# VALVEBOARD_ValveDrive4.net
KiCad netlist of a schematic drawn in Altium Designer
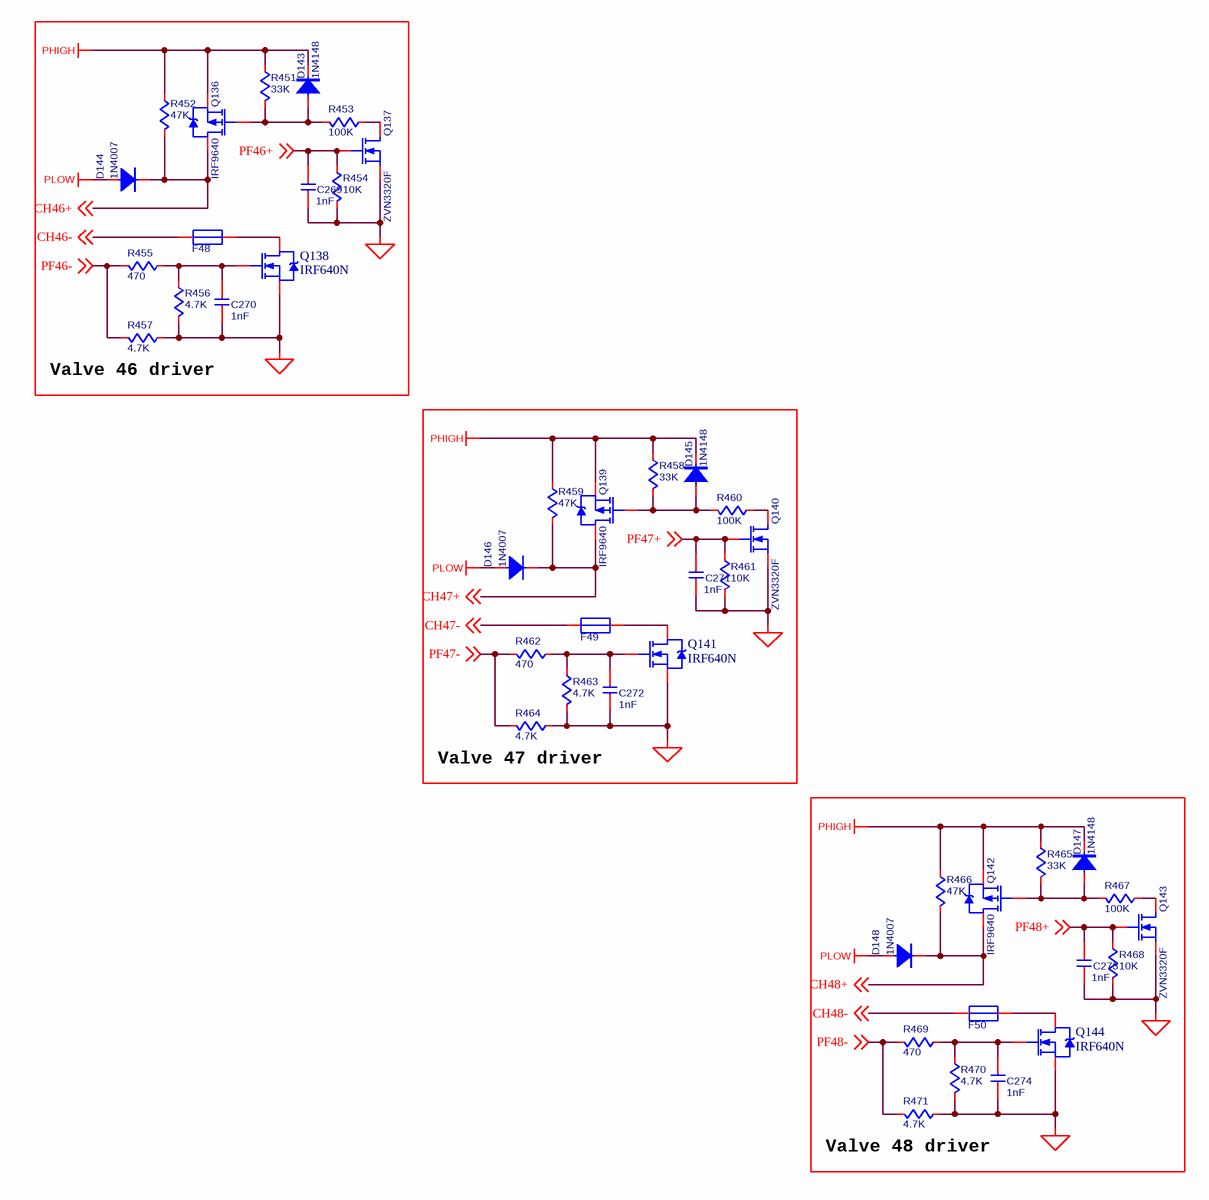
[diagram p0: VALVEBOARD_ValveDrive4.SchDoc]

(export (version "E")
  (design (tool "Eeschema 10.0.6"))
  (components
    (comp (ref "C269")
      (value "1nF")
      (footprint "zynq:C0603")
      (fields (field (name "VOLTAGE") "25V") (field (name "Comment") "C-NOMO"))
      (libsource (lib "zynq") (part "C-NOMO"))
    )
    (comp (ref "C270")
      (value "1nF")
      (footprint "zynq:C0603")
      (fields (field (name "VOLTAGE") "25V") (field (name "Comment") "C-NOMO"))
      (libsource (lib "zynq") (part "C-NOMO"))
    )
    (comp (ref "C271")
      (value "1nF")
      (footprint "zynq:C0603")
      (fields (field (name "VOLTAGE") "25V") (field (name "Comment") "C-NOMO"))
      (libsource (lib "zynq") (part "C-NOMO"))
    )
    (comp (ref "C272")
      (value "1nF")
      (footprint "zynq:C0603")
      (fields (field (name "VOLTAGE") "25V") (field (name "Comment") "C-NOMO"))
      (libsource (lib "zynq") (part "C-NOMO"))
    )
    (comp (ref "C273")
      (value "1nF")
      (footprint "zynq:C0603")
      (fields (field (name "VOLTAGE") "25V") (field (name "Comment") "C-NOMO"))
      (libsource (lib "zynq") (part "C-NOMO"))
    )
    (comp (ref "C274")
      (value "1nF")
      (footprint "zynq:C0603")
      (fields (field (name "VOLTAGE") "25V") (field (name "Comment") "C-NOMO"))
      (libsource (lib "zynq") (part "C-NOMO"))
    )
    (comp (ref "D143") (value "1N4148") (footprint "SOD-123") (libsource (lib "zynq") (part "DIOD1")))
    (comp (ref "D144") (value "1N4007") (footprint "zynq:1N4148") (libsource (lib "") (part "DIOD1_1")))
    (comp (ref "D145") (value "1N4148") (footprint "SOD-123") (libsource (lib "zynq") (part "DIOD1")))
    (comp (ref "D146") (value "1N4007") (footprint "zynq:1N4148") (libsource (lib "") (part "DIOD1_1")))
    (comp (ref "D147") (value "1N4148") (footprint "SOD-123") (libsource (lib "zynq") (part "DIOD1")))
    (comp (ref "D148") (value "1N4007") (footprint "zynq:1N4148") (libsource (lib "") (part "DIOD1_1")))
    (comp (ref "F48") (value "F50") (footprint "zynq:F-TH") (libsource (lib "zynq") (part "F50")))
    (comp (ref "F49") (value "F50") (footprint "zynq:F-TH") (libsource (lib "zynq") (part "F50")))
    (comp (ref "F50") (value "F50") (footprint "zynq:F-TH") (libsource (lib "zynq") (part "F50")))
    (comp (ref "Q136")
      (value "IRF9640")
      (footprint "TO-220AB")
      (description "P-Channel Power MOSFET")
      (fields (field (name "PUBLISHER") "Altium Limited"))
      (libsource (lib "zynq") (part "IRF9640"))
    )
    (comp (ref "Q137")
      (value "ZVN3320F")
      (footprint "zynq:ZVN3320F")
      (description "N-Channel MOSFET")
      (fields (field (name "PUBLISHER") "Altium Limited"))
      (libsource (lib "zynq") (part "ZVN3320F"))
    )
    (comp (ref "Q138")
      (value "IRF640N")
      (footprint "zynq:TO-220AB")
      (description "N-Channel Power MOSFET")
      (fields (field (name "PUBLISHER") "Altium Limited"))
      (libsource (lib "zynq") (part "IRF640N"))
    )
    (comp (ref "Q139")
      (value "IRF9640")
      (footprint "TO-220AB")
      (description "P-Channel Power MOSFET")
      (fields (field (name "PUBLISHER") "Altium Limited"))
      (libsource (lib "zynq") (part "IRF9640"))
    )
    (comp (ref "Q140")
      (value "ZVN3320F")
      (footprint "zynq:ZVN3320F")
      (description "N-Channel MOSFET")
      (fields (field (name "PUBLISHER") "Altium Limited"))
      (libsource (lib "zynq") (part "ZVN3320F"))
    )
    (comp (ref "Q141")
      (value "IRF640N")
      (footprint "zynq:TO-220AB")
      (description "N-Channel Power MOSFET")
      (fields (field (name "PUBLISHER") "Altium Limited"))
      (libsource (lib "zynq") (part "IRF640N"))
    )
    (comp (ref "Q142")
      (value "IRF9640")
      (footprint "TO-220AB")
      (description "P-Channel Power MOSFET")
      (fields (field (name "PUBLISHER") "Altium Limited"))
      (libsource (lib "zynq") (part "IRF9640"))
    )
    (comp (ref "Q143")
      (value "ZVN3320F")
      (footprint "zynq:ZVN3320F")
      (description "N-Channel MOSFET")
      (fields (field (name "PUBLISHER") "Altium Limited"))
      (libsource (lib "zynq") (part "ZVN3320F"))
    )
    (comp (ref "Q144")
      (value "IRF640N")
      (footprint "zynq:TO-220AB")
      (description "N-Channel Power MOSFET")
      (fields (field (name "PUBLISHER") "Altium Limited"))
      (libsource (lib "zynq") (part "IRF640N"))
    )
    (comp (ref "R451")
      (value "33K")
      (footprint "zynq:R0603")
      (fields (field (name "Comment") "R"))
      (libsource (lib "zynq") (part "R"))
    )
    (comp (ref "R452")
      (value "47K")
      (footprint "R2512")
      (fields (field (name "Comment") "R"))
      (libsource (lib "zynq") (part "R"))
    )
    (comp (ref "R453")
      (value "100K")
      (footprint "zynq:R0603")
      (fields (field (name "Comment") "R"))
      (libsource (lib "zynq") (part "R"))
    )
    (comp (ref "R454")
      (value "10K")
      (footprint "zynq:R0603")
      (fields (field (name "Comment") "R"))
      (libsource (lib "zynq") (part "R"))
    )
    (comp (ref "R455")
      (value "470")
      (footprint "zynq:R0402")
      (fields (field (name "Comment") "R"))
      (libsource (lib "zynq") (part "R"))
    )
    (comp (ref "R456")
      (value "4.7K")
      (footprint "zynq:R0402")
      (fields (field (name "Comment") "R"))
      (libsource (lib "zynq") (part "R"))
    )
    (comp (ref "R457")
      (value "4.7K")
      (footprint "zynq:R0402")
      (fields (field (name "Comment") "R"))
      (libsource (lib "zynq") (part "R"))
    )
    (comp (ref "R458")
      (value "33K")
      (footprint "zynq:R0603")
      (fields (field (name "Comment") "R"))
      (libsource (lib "zynq") (part "R"))
    )
    (comp (ref "R459")
      (value "47K")
      (footprint "R2512")
      (fields (field (name "Comment") "R"))
      (libsource (lib "zynq") (part "R"))
    )
    (comp (ref "R460")
      (value "100K")
      (footprint "zynq:R0603")
      (fields (field (name "Comment") "R"))
      (libsource (lib "zynq") (part "R"))
    )
    (comp (ref "R461")
      (value "10K")
      (footprint "zynq:R0603")
      (fields (field (name "Comment") "R"))
      (libsource (lib "zynq") (part "R"))
    )
    (comp (ref "R462")
      (value "470")
      (footprint "zynq:R0402")
      (fields (field (name "Comment") "R"))
      (libsource (lib "zynq") (part "R"))
    )
    (comp (ref "R463")
      (value "4.7K")
      (footprint "zynq:R0402")
      (fields (field (name "Comment") "R"))
      (libsource (lib "zynq") (part "R"))
    )
    (comp (ref "R464")
      (value "4.7K")
      (footprint "zynq:R0402")
      (fields (field (name "Comment") "R"))
      (libsource (lib "zynq") (part "R"))
    )
    (comp (ref "R465")
      (value "33K")
      (footprint "zynq:R0603")
      (fields (field (name "Comment") "R"))
      (libsource (lib "zynq") (part "R"))
    )
    (comp (ref "R466")
      (value "47K")
      (footprint "R2512")
      (fields (field (name "Comment") "R"))
      (libsource (lib "zynq") (part "R"))
    )
    (comp (ref "R467")
      (value "100K")
      (footprint "zynq:R0603")
      (fields (field (name "Comment") "R"))
      (libsource (lib "zynq") (part "R"))
    )
    (comp (ref "R468")
      (value "10K")
      (footprint "zynq:R0603")
      (fields (field (name "Comment") "R"))
      (libsource (lib "zynq") (part "R"))
    )
    (comp (ref "R469")
      (value "470")
      (footprint "zynq:R0402")
      (fields (field (name "Comment") "R"))
      (libsource (lib "zynq") (part "R"))
    )
    (comp (ref "R470")
      (value "4.7K")
      (footprint "zynq:R0402")
      (fields (field (name "Comment") "R"))
      (libsource (lib "zynq") (part "R"))
    )
    (comp (ref "R471")
      (value "4.7K")
      (footprint "zynq:R0402")
      (fields (field (name "Comment") "R"))
      (libsource (lib "zynq") (part "R"))
    )
  )
  (nets
    (net (code "1") (name "CH46+") (class "Default")
      (node (ref "D144") (pin "1") (pinfunction "1_1") (pintype "passive"))
      (node (ref "Q136") (pin "2") (pinfunction "D_2") (pintype "passive"))
      (node (ref "R452") (pin "1") (pinfunction "1_1") (pintype "passive"))
    )
    (net (code "2") (name "CH46-") (class "Default") (node (ref "F48") (pin "1") (pintype "passive")))
    (net (code "3") (name "CH47+") (class "Default")
      (node (ref "D146") (pin "1") (pinfunction "1_1") (pintype "passive"))
      (node (ref "Q139") (pin "2") (pinfunction "D_2") (pintype "passive"))
      (node (ref "R459") (pin "1") (pinfunction "1_1") (pintype "passive"))
    )
    (net (code "4") (name "CH47-") (class "Default") (node (ref "F49") (pin "1") (pintype "passive")))
    (net (code "5") (name "CH48+") (class "Default")
      (node (ref "D148") (pin "1") (pinfunction "1_1") (pintype "passive"))
      (node (ref "Q142") (pin "2") (pinfunction "D_2") (pintype "passive"))
      (node (ref "R466") (pin "1") (pinfunction "1_1") (pintype "passive"))
    )
    (net (code "6") (name "CH48-") (class "Default") (node (ref "F50") (pin "1") (pintype "passive")))
    (net (code "7") (name "Net-(Q136-G)") (class "Default")
      (node (ref "D143") (pin "2") (pinfunction "2_2") (pintype "passive"))
      (node (ref "Q136") (pin "1") (pinfunction "G_1") (pintype "passive"))
      (node (ref "R451") (pin "1") (pinfunction "1_1") (pintype "passive"))
      (node (ref "R453") (pin "1") (pinfunction "1_1") (pintype "passive"))
    )
    (net (code "8") (name "Net-(Q137-D)") (class "Default")
      (node (ref "Q137") (pin "1") (pinfunction "D_1") (pintype "passive"))
      (node (ref "R453") (pin "2") (pinfunction "2_2") (pintype "passive"))
    )
    (net (code "9") (name "Net-(Q138-D)") (class "Default")
      (node (ref "F48") (pin "2") (pintype "passive"))
      (node (ref "Q138") (pin "2") (pinfunction "D_2") (pintype "passive"))
    )
    (net (code "10") (name "Net-(Q138-G)") (class "Default")
      (node (ref "C270") (pin "2") (pinfunction "2_2") (pintype "passive"))
      (node (ref "Q138") (pin "1") (pinfunction "G_1") (pintype "passive"))
      (node (ref "R455") (pin "2") (pinfunction "2_2") (pintype "passive"))
      (node (ref "R456") (pin "2") (pinfunction "2_2") (pintype "passive"))
    )
    (net (code "11") (name "Net-(Q139-G)") (class "Default")
      (node (ref "D145") (pin "2") (pinfunction "2_2") (pintype "passive"))
      (node (ref "Q139") (pin "1") (pinfunction "G_1") (pintype "passive"))
      (node (ref "R458") (pin "1") (pinfunction "1_1") (pintype "passive"))
      (node (ref "R460") (pin "1") (pinfunction "1_1") (pintype "passive"))
    )
    (net (code "12") (name "Net-(Q140-D)") (class "Default")
      (node (ref "Q140") (pin "1") (pinfunction "D_1") (pintype "passive"))
      (node (ref "R460") (pin "2") (pinfunction "2_2") (pintype "passive"))
    )
    (net (code "13") (name "Net-(Q141-D)") (class "Default")
      (node (ref "F49") (pin "2") (pintype "passive"))
      (node (ref "Q141") (pin "2") (pinfunction "D_2") (pintype "passive"))
    )
    (net (code "14") (name "Net-(Q141-G)") (class "Default")
      (node (ref "C272") (pin "2") (pinfunction "2_2") (pintype "passive"))
      (node (ref "Q141") (pin "1") (pinfunction "G_1") (pintype "passive"))
      (node (ref "R462") (pin "2") (pinfunction "2_2") (pintype "passive"))
      (node (ref "R463") (pin "2") (pinfunction "2_2") (pintype "passive"))
    )
    (net (code "15") (name "Net-(Q142-G)") (class "Default")
      (node (ref "D147") (pin "2") (pinfunction "2_2") (pintype "passive"))
      (node (ref "Q142") (pin "1") (pinfunction "G_1") (pintype "passive"))
      (node (ref "R465") (pin "1") (pinfunction "1_1") (pintype "passive"))
      (node (ref "R467") (pin "1") (pinfunction "1_1") (pintype "passive"))
    )
    (net (code "16") (name "Net-(Q143-D)") (class "Default")
      (node (ref "Q143") (pin "1") (pinfunction "D_1") (pintype "passive"))
      (node (ref "R467") (pin "2") (pinfunction "2_2") (pintype "passive"))
    )
    (net (code "17") (name "Net-(Q144-D)") (class "Default")
      (node (ref "F50") (pin "2") (pintype "passive"))
      (node (ref "Q144") (pin "2") (pinfunction "D_2") (pintype "passive"))
    )
    (net (code "18") (name "Net-(Q144-G)") (class "Default")
      (node (ref "C274") (pin "2") (pinfunction "2_2") (pintype "passive"))
      (node (ref "Q144") (pin "1") (pinfunction "G_1") (pintype "passive"))
      (node (ref "R469") (pin "2") (pinfunction "2_2") (pintype "passive"))
      (node (ref "R470") (pin "2") (pinfunction "2_2") (pintype "passive"))
    )
    (net (code "19") (name "PF46+") (class "Default")
      (node (ref "C269") (pin "2") (pinfunction "2_2") (pintype "passive"))
      (node (ref "Q137") (pin "2") (pinfunction "G_2") (pintype "passive"))
      (node (ref "R454") (pin "2") (pinfunction "2_2") (pintype "passive"))
    )
    (net (code "20") (name "PF46-") (class "Default")
      (node (ref "R455") (pin "1") (pinfunction "1_1") (pintype "passive"))
      (node (ref "R457") (pin "1") (pinfunction "1_1") (pintype "passive"))
    )
    (net (code "21") (name "PF47+") (class "Default")
      (node (ref "C271") (pin "2") (pinfunction "2_2") (pintype "passive"))
      (node (ref "Q140") (pin "2") (pinfunction "G_2") (pintype "passive"))
      (node (ref "R461") (pin "2") (pinfunction "2_2") (pintype "passive"))
    )
    (net (code "22") (name "PF47-") (class "Default")
      (node (ref "R462") (pin "1") (pinfunction "1_1") (pintype "passive"))
      (node (ref "R464") (pin "1") (pinfunction "1_1") (pintype "passive"))
    )
    (net (code "23") (name "PF48+") (class "Default")
      (node (ref "C273") (pin "2") (pinfunction "2_2") (pintype "passive"))
      (node (ref "Q143") (pin "2") (pinfunction "G_2") (pintype "passive"))
      (node (ref "R468") (pin "2") (pinfunction "2_2") (pintype "passive"))
    )
    (net (code "24") (name "PF48-") (class "Default")
      (node (ref "R469") (pin "1") (pinfunction "1_1") (pintype "passive"))
      (node (ref "R471") (pin "1") (pinfunction "1_1") (pintype "passive"))
    )
    (net (code "25") (name "PGND") (class "Default")
      (node (ref "C269") (pin "1") (pinfunction "1_1") (pintype "passive"))
      (node (ref "C270") (pin "1") (pinfunction "1_1") (pintype "passive"))
      (node (ref "C271") (pin "1") (pinfunction "1_1") (pintype "passive"))
      (node (ref "C272") (pin "1") (pinfunction "1_1") (pintype "passive"))
      (node (ref "C273") (pin "1") (pinfunction "1_1") (pintype "passive"))
      (node (ref "C274") (pin "1") (pinfunction "1_1") (pintype "passive"))
      (node (ref "Q137") (pin "3") (pinfunction "S_3") (pintype "passive"))
      (node (ref "Q138") (pin "3") (pinfunction "S_3") (pintype "passive"))
      (node (ref "Q140") (pin "3") (pinfunction "S_3") (pintype "passive"))
      (node (ref "Q141") (pin "3") (pinfunction "S_3") (pintype "passive"))
      (node (ref "Q143") (pin "3") (pinfunction "S_3") (pintype "passive"))
      (node (ref "Q144") (pin "3") (pinfunction "S_3") (pintype "passive"))
      (node (ref "R454") (pin "1") (pinfunction "1_1") (pintype "passive"))
      (node (ref "R456") (pin "1") (pinfunction "1_1") (pintype "passive"))
      (node (ref "R457") (pin "2") (pinfunction "2_2") (pintype "passive"))
      (node (ref "R461") (pin "1") (pinfunction "1_1") (pintype "passive"))
      (node (ref "R463") (pin "1") (pinfunction "1_1") (pintype "passive"))
      (node (ref "R464") (pin "2") (pinfunction "2_2") (pintype "passive"))
      (node (ref "R468") (pin "1") (pinfunction "1_1") (pintype "passive"))
      (node (ref "R470") (pin "1") (pinfunction "1_1") (pintype "passive"))
      (node (ref "R471") (pin "2") (pinfunction "2_2") (pintype "passive"))
    )
    (net (code "26") (name "PHIGH") (class "Default")
      (node (ref "D143") (pin "1") (pinfunction "1_1") (pintype "passive"))
      (node (ref "D145") (pin "1") (pinfunction "1_1") (pintype "passive"))
      (node (ref "D147") (pin "1") (pinfunction "1_1") (pintype "passive"))
      (node (ref "Q136") (pin "3") (pinfunction "S_3") (pintype "passive"))
      (node (ref "Q139") (pin "3") (pinfunction "S_3") (pintype "passive"))
      (node (ref "Q142") (pin "3") (pinfunction "S_3") (pintype "passive"))
      (node (ref "R451") (pin "2") (pinfunction "2_2") (pintype "passive"))
      (node (ref "R452") (pin "2") (pinfunction "2_2") (pintype "passive"))
      (node (ref "R458") (pin "2") (pinfunction "2_2") (pintype "passive"))
      (node (ref "R459") (pin "2") (pinfunction "2_2") (pintype "passive"))
      (node (ref "R465") (pin "2") (pinfunction "2_2") (pintype "passive"))
      (node (ref "R466") (pin "2") (pinfunction "2_2") (pintype "passive"))
    )
    (net (code "27") (name "PLOW") (class "Default")
      (node (ref "D144") (pin "2") (pinfunction "2_2") (pintype "passive"))
      (node (ref "D146") (pin "2") (pinfunction "2_2") (pintype "passive"))
      (node (ref "D148") (pin "2") (pinfunction "2_2") (pintype "passive"))
    )
  )
)
